# DVI_D_Out.net
KiCad netlist of a schematic drawn in Altium Designer
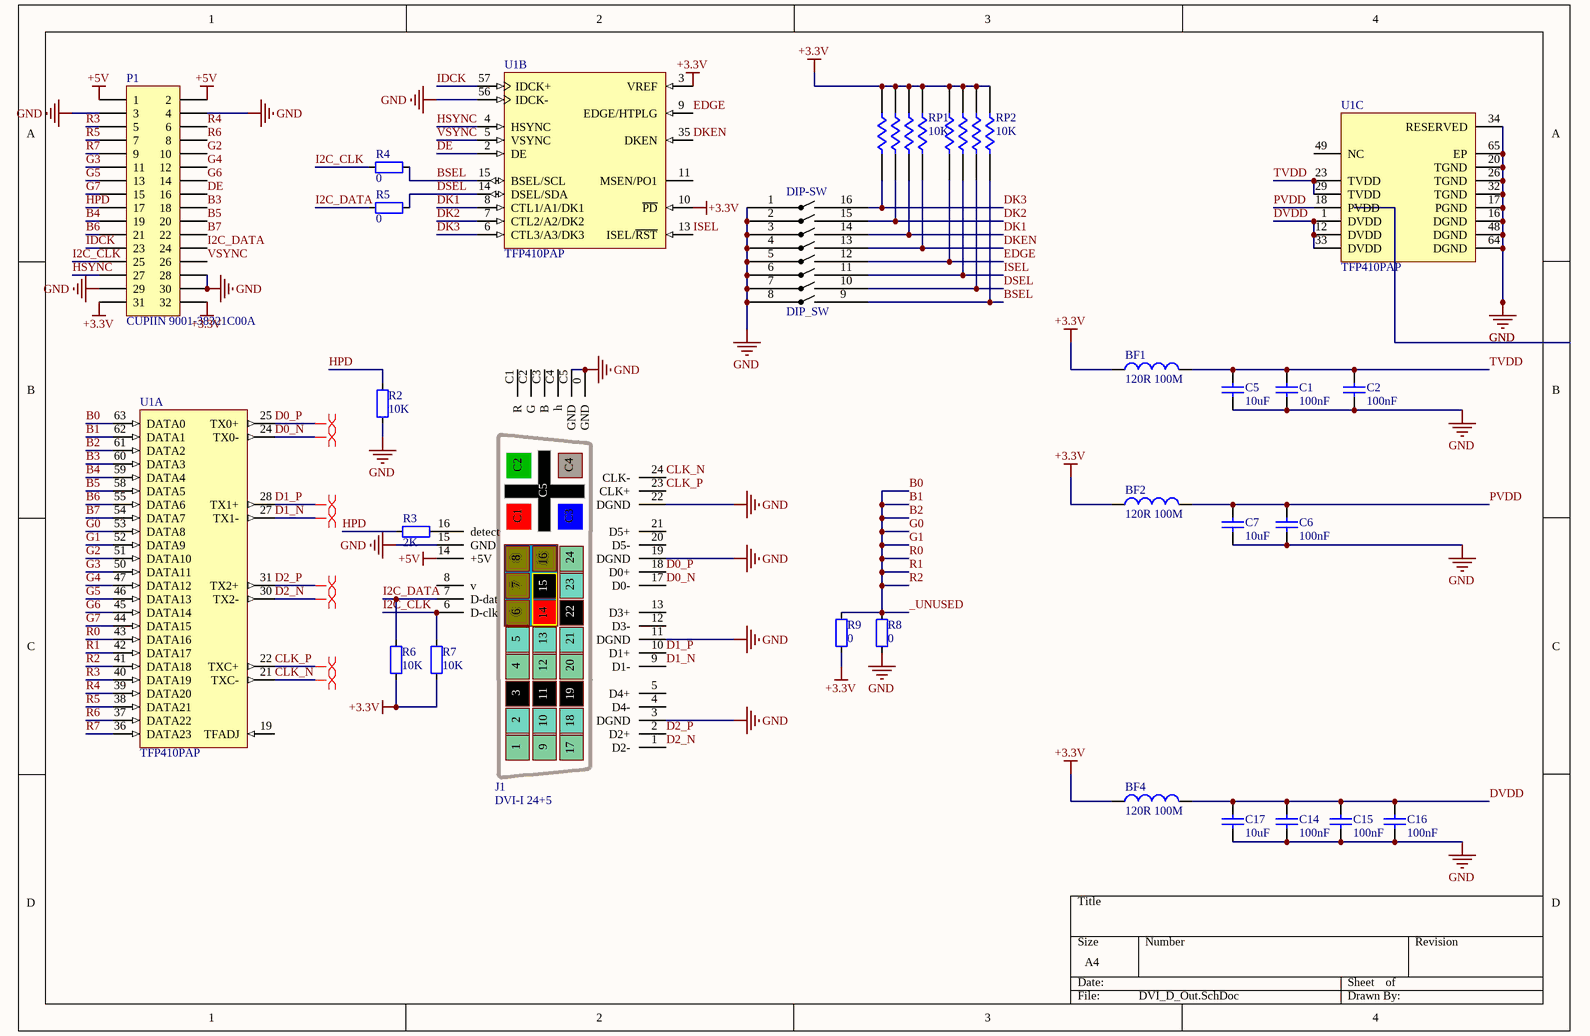
[diagram p0: DVI_D_Out.SchDoc]

(export (version "E")
  (design (tool "Eeschema 10.0.6"))
  (components
    (comp (ref "BF1")
      (value "120R 100M")
      (footprint "L-1608[0603]")
      (fields (field (name "Comment") "GZ1608D121TF") (field (name "PUBLISHER") "Altium Limited"))
      (libsource (lib "Miscellaneous Devices") (part "Inductor"))
    )
    (comp (ref "BF2")
      (value "120R 100M")
      (footprint "L-1608[0603]")
      (fields (field (name "Comment") "GZ1608D121TF") (field (name "PUBLISHER") "Altium Limited"))
      (libsource (lib "Miscellaneous Devices") (part "Inductor"))
    )
    (comp (ref "BF4")
      (value "120R 100M")
      (footprint "L-1608[0603]")
      (fields (field (name "Comment") "GZ1608D121TF") (field (name "PUBLISHER") "Altium Limited"))
      (libsource (lib "Miscellaneous Devices") (part "Inductor"))
    )
    (comp (ref "C1")
      (value "100nF")
      (footprint "C-1608[0603]")
      (description "Capacitor (Semiconductor SIM Model)")
      (fields (field (name "Comment") "Cap Semi") (field (name "PUBLISHER") "Altium Limited"))
      (libsource (lib "Miscellaneous Devices") (part "Cap Semi"))
    )
    (comp (ref "C2")
      (value "100nF")
      (footprint "C-1608[0603]")
      (description "Capacitor (Semiconductor SIM Model)")
      (fields (field (name "Comment") "Cap Semi") (field (name "PUBLISHER") "Altium Limited"))
      (libsource (lib "Miscellaneous Devices") (part "Cap Semi"))
    )
    (comp (ref "C5")
      (value "10uF")
      (footprint "C-1608[0603]")
      (description "Capacitor (Semiconductor SIM Model)")
      (fields (field (name "Comment") "Cap Semi") (field (name "PUBLISHER") "Altium Limited"))
      (libsource (lib "Miscellaneous Devices") (part "Cap Semi"))
    )
    (comp (ref "C6")
      (value "100nF")
      (footprint "C-1608[0603]")
      (description "Capacitor (Semiconductor SIM Model)")
      (fields (field (name "Comment") "Cap Semi") (field (name "PUBLISHER") "Altium Limited"))
      (libsource (lib "Miscellaneous Devices") (part "Cap Semi"))
    )
    (comp (ref "C7")
      (value "10uF")
      (footprint "C-1608[0603]")
      (description "Capacitor (Semiconductor SIM Model)")
      (fields (field (name "Comment") "Cap Semi") (field (name "PUBLISHER") "Altium Limited"))
      (libsource (lib "Miscellaneous Devices") (part "Cap Semi"))
    )
    (comp (ref "C14")
      (value "100nF")
      (footprint "C-1608[0603]")
      (description "Capacitor (Semiconductor SIM Model)")
      (fields (field (name "Comment") "Cap Semi") (field (name "PUBLISHER") "Altium Limited"))
      (libsource (lib "Miscellaneous Devices") (part "Cap Semi"))
    )
    (comp (ref "C15")
      (value "100nF")
      (footprint "C-1608[0603]")
      (description "Capacitor (Semiconductor SIM Model)")
      (fields (field (name "Comment") "Cap Semi") (field (name "PUBLISHER") "Altium Limited"))
      (libsource (lib "Miscellaneous Devices") (part "Cap Semi"))
    )
    (comp (ref "C16")
      (value "100nF")
      (footprint "C-1608[0603]")
      (description "Capacitor (Semiconductor SIM Model)")
      (fields (field (name "Comment") "Cap Semi") (field (name "PUBLISHER") "Altium Limited"))
      (libsource (lib "Miscellaneous Devices") (part "Cap Semi"))
    )
    (comp (ref "C17")
      (value "10uF")
      (footprint "C-1608[0603]")
      (description "Capacitor (Semiconductor SIM Model)")
      (fields (field (name "Comment") "Cap Semi") (field (name "PUBLISHER") "Altium Limited"))
      (libsource (lib "Miscellaneous Devices") (part "Cap Semi"))
    )
    (comp (ref "DIP-SW") (value "DIP_SW") (footprint "SO16W") (libsource (lib "Schlib1") (part "DIP_SW")))
    (comp (ref "J1") (value "DVI-I 24+5") (footprint "DVI-I") (libsource (lib "DVI-I") (part "DVI-I")))
    (comp (ref "P1")
      (value "CUPIIN 9001-38321C00A")
      (footprint "OUPIIN 9001-38321C00A")
      (description "Header, 16-Pin, Dual row")
      (fields (field (name "PUBLISHER") "Altium Limited"))
      (libsource (lib "Miscellaneous Connectors") (part "Header 16X2"))
    )
    (comp (ref "R2")
      (value "10K")
      (footprint "PCB_PassiveRes:RES_0603")
      (description "Resistor")
      (fields (field (name "Comment") "Res_0603"))
      (libsource (lib "") (part "Res_0603_1"))
    )
    (comp (ref "R3")
      (value "2K")
      (footprint "PCB_PassiveRes:RES_0603")
      (description "Resistor")
      (fields (field (name "Comment") "Res_0603"))
      (libsource (lib "") (part "Res_0603_2"))
    )
    (comp (ref "R4")
      (value "0")
      (footprint "PCB_PassiveRes:RES_0603")
      (description "Resistor")
      (fields (field (name "Comment") "Res_0603"))
      (libsource (lib "") (part "Res_0603_2"))
    )
    (comp (ref "R5")
      (value "0")
      (footprint "PCB_PassiveRes:RES_0603")
      (description "Resistor")
      (fields (field (name "Comment") "Res_0603"))
      (libsource (lib "") (part "Res_0603_2"))
    )
    (comp (ref "R6")
      (value "10K")
      (footprint "PCB_PassiveRes:RES_0603")
      (description "Resistor")
      (fields (field (name "Comment") "Res_0603"))
      (libsource (lib "SCH_Passive") (part "Res_0603"))
    )
    (comp (ref "R7")
      (value "10K")
      (footprint "PCB_PassiveRes:RES_0603")
      (description "Resistor")
      (fields (field (name "Comment") "Res_0603"))
      (libsource (lib "SCH_Passive") (part "Res_0603"))
    )
    (comp (ref "R8")
      (value "0")
      (footprint "PCB_PassiveRes:RES_0603")
      (description "Resistor")
      (fields (field (name "Comment") "Res_0603"))
      (libsource (lib "SCH_Passive") (part "Res_0603"))
    )
    (comp (ref "R9")
      (value "0")
      (footprint "PCB_PassiveRes:RES_0603")
      (description "Resistor")
      (fields (field (name "Comment") "Res_0603"))
      (libsource (lib "SCH_Passive") (part "Res_0603"))
    )
    (comp (ref "RP1") (value "10K") (footprint "R0603x4") (libsource (lib "general") (part "RPACK4")))
    (comp (ref "RP2") (value "10K") (footprint "R0603x4") (libsource (lib "general") (part "RPACK4")))
    (comp (ref "U1")
      (value "TFP410PAP")
      (footprint "PAP64-4650X4650TP_N")
      (fields (field (name "MANUFACTURER") "Texas Instruments"))
      (libsource (lib "Altium Content Vault") (part "CMP-0325-00079-1"))
    )
  )
  (nets
    (net (code "1") (name "+3.3V") (class "Default")
      (node (ref "BF1") (pin "1") (pinfunction "1_1") (pintype "passive"))
      (node (ref "BF2") (pin "1") (pinfunction "1_1") (pintype "passive"))
      (node (ref "BF4") (pin "1") (pinfunction "1_1") (pintype "passive"))
      (node (ref "P1") (pin "31") (pinfunction "31_31") (pintype "passive"))
      (node (ref "P1") (pin "32") (pinfunction "32_32") (pintype "passive"))
      (node (ref "R6") (pin "2") (pinfunction "2_2") (pintype "passive"))
      (node (ref "R7") (pin "2") (pinfunction "2_2") (pintype "passive"))
      (node (ref "R9") (pin "2") (pinfunction "2_2") (pintype "passive"))
      (node (ref "RP1") (pin "5") (pinfunction "5_5") (pintype "passive"))
      (node (ref "RP1") (pin "6") (pinfunction "6_6") (pintype "passive"))
      (node (ref "RP1") (pin "7") (pinfunction "7_7") (pintype "passive"))
      (node (ref "RP1") (pin "8") (pinfunction "8_8") (pintype "passive"))
      (node (ref "RP2") (pin "5") (pinfunction "5_5") (pintype "passive"))
      (node (ref "RP2") (pin "6") (pinfunction "6_6") (pintype "passive"))
      (node (ref "RP2") (pin "7") (pinfunction "7_7") (pintype "passive"))
      (node (ref "RP2") (pin "8") (pinfunction "8_8") (pintype "passive"))
      (node (ref "U1") (pin "10") (pinfunction "~{PD}_10") (pintype "input"))
      (node (ref "U1") (pin "3") (pinfunction "VREF_3") (pintype "input"))
    )
    (net (code "2") (name "+5V") (class "Default")
      (node (ref "J1") (pin "14") (pinfunction "+5V_14") (pintype "passive"))
      (node (ref "P1") (pin "1") (pinfunction "1_1") (pintype "passive"))
      (node (ref "P1") (pin "2") (pinfunction "2_2") (pintype "passive"))
    )
    (net (code "3") (name "/B0") (class "Default")
      (node (ref "R8") (pin "1") (pinfunction "1_1") (pintype "passive"))
      (node (ref "R9") (pin "1") (pinfunction "1_1") (pintype "passive"))
      (node (ref "U1") (pin "41") (pinfunction "DATA18_41") (pintype "input"))
      (node (ref "U1") (pin "42") (pinfunction "DATA17_42") (pintype "input"))
      (node (ref "U1") (pin "43") (pinfunction "DATA16_43") (pintype "input"))
      (node (ref "U1") (pin "52") (pinfunction "DATA9_52") (pintype "input"))
      (node (ref "U1") (pin "53") (pinfunction "DATA8_53") (pintype "input"))
      (node (ref "U1") (pin "61") (pinfunction "DATA2_61") (pintype "input"))
      (node (ref "U1") (pin "62") (pinfunction "DATA1_62") (pintype "input"))
      (node (ref "U1") (pin "63") (pinfunction "DATA0_63") (pintype "input"))
    )
    (net (code "4") (name "/B3") (class "Default")
      (node (ref "P1") (pin "18") (pinfunction "18_18") (pintype "passive"))
      (node (ref "U1") (pin "60") (pinfunction "DATA3_60") (pintype "input"))
    )
    (net (code "5") (name "/B4") (class "Default")
      (node (ref "P1") (pin "19") (pinfunction "19_19") (pintype "passive"))
      (node (ref "U1") (pin "59") (pinfunction "DATA4_59") (pintype "input"))
    )
    (net (code "6") (name "/B5") (class "Default")
      (node (ref "P1") (pin "20") (pinfunction "20_20") (pintype "passive"))
      (node (ref "U1") (pin "58") (pinfunction "DATA5_58") (pintype "input"))
    )
    (net (code "7") (name "/B6") (class "Default")
      (node (ref "P1") (pin "21") (pinfunction "21_21") (pintype "passive"))
      (node (ref "U1") (pin "55") (pinfunction "DATA6_55") (pintype "input"))
    )
    (net (code "8") (name "/B7") (class "Default")
      (node (ref "P1") (pin "22") (pinfunction "22_22") (pintype "passive"))
      (node (ref "U1") (pin "54") (pinfunction "DATA7_54") (pintype "input"))
    )
    (net (code "9") (name "/BSEL") (class "Default")
      (node (ref "DIP-SW") (pin "9") (pinfunction "9_9") (pintype "passive"))
      (node (ref "R4") (pin "1") (pinfunction "1_1") (pintype "passive"))
      (node (ref "RP2") (pin "4") (pinfunction "4_4") (pintype "passive"))
      (node (ref "U1") (pin "15") (pinfunction "BSEL/SCL_15") (pintype "bidirectional"))
    )
    (net (code "10") (name "/CLK_N") (class "Default")
      (node (ref "J1") (pin "24") (pinfunction "CLK-_24") (pintype "passive"))
      (node (ref "U1") (pin "21") (pinfunction "TXC-_21") (pintype "output"))
    )
    (net (code "11") (name "/CLK_P") (class "Default")
      (node (ref "J1") (pin "23") (pinfunction "CLK+_23") (pintype "passive"))
      (node (ref "U1") (pin "22") (pinfunction "TXC+_22") (pintype "output"))
    )
    (net (code "12") (name "/D0_N") (class "Default")
      (node (ref "J1") (pin "17") (pinfunction "D0-_17") (pintype "passive"))
      (node (ref "U1") (pin "24") (pinfunction "TX0-_24") (pintype "output"))
    )
    (net (code "13") (name "/D0_P") (class "Default")
      (node (ref "J1") (pin "18") (pinfunction "D0+_18") (pintype "passive"))
      (node (ref "U1") (pin "25") (pinfunction "TX0+_25") (pintype "output"))
    )
    (net (code "14") (name "/D1_N") (class "Default")
      (node (ref "J1") (pin "9") (pinfunction "D1-_9") (pintype "passive"))
      (node (ref "U1") (pin "27") (pinfunction "TX1-_27") (pintype "output"))
    )
    (net (code "15") (name "/D1_P") (class "Default")
      (node (ref "J1") (pin "10") (pinfunction "D1+_10") (pintype "passive"))
      (node (ref "U1") (pin "28") (pinfunction "TX1+_28") (pintype "output"))
    )
    (net (code "16") (name "/D2_N") (class "Default")
      (node (ref "J1") (pin "1") (pinfunction "D2-_1") (pintype "passive"))
      (node (ref "U1") (pin "30") (pinfunction "TX2-_30") (pintype "output"))
    )
    (net (code "17") (name "/D2_P") (class "Default")
      (node (ref "J1") (pin "2") (pinfunction "D2+_2") (pintype "passive"))
      (node (ref "U1") (pin "31") (pinfunction "TX2+_31") (pintype "output"))
    )
    (net (code "18") (name "/DE") (class "Default")
      (node (ref "P1") (pin "16") (pinfunction "16_16") (pintype "passive"))
      (node (ref "U1") (pin "2") (pinfunction "DE_2") (pintype "input"))
    )
    (net (code "19") (name "/DK1") (class "Default")
      (node (ref "DIP-SW") (pin "14") (pinfunction "14_14") (pintype "passive"))
      (node (ref "RP1") (pin "3") (pinfunction "3_3") (pintype "passive"))
      (node (ref "U1") (pin "8") (pinfunction "CTL1/A1/DK1_8") (pintype "input"))
    )
    (net (code "20") (name "/DK2") (class "Default")
      (node (ref "DIP-SW") (pin "15") (pinfunction "15_15") (pintype "passive"))
      (node (ref "RP1") (pin "2") (pinfunction "2_2") (pintype "passive"))
      (node (ref "U1") (pin "7") (pinfunction "CTL2/A2/DK2_7") (pintype "input"))
    )
    (net (code "21") (name "/DK3") (class "Default")
      (node (ref "DIP-SW") (pin "16") (pinfunction "16_16") (pintype "passive"))
      (node (ref "RP1") (pin "1") (pinfunction "1_1") (pintype "passive"))
      (node (ref "U1") (pin "6") (pinfunction "CTL3/A3/DK3_6") (pintype "input"))
    )
    (net (code "22") (name "/DKEN") (class "Default")
      (node (ref "DIP-SW") (pin "13") (pinfunction "13_13") (pintype "passive"))
      (node (ref "RP1") (pin "4") (pinfunction "4_4") (pintype "passive"))
      (node (ref "U1") (pin "35") (pinfunction "DKEN_35") (pintype "input"))
    )
    (net (code "23") (name "/DSEL") (class "Default")
      (node (ref "DIP-SW") (pin "10") (pinfunction "10_10") (pintype "passive"))
      (node (ref "R5") (pin "1") (pinfunction "1_1") (pintype "passive"))
      (node (ref "RP2") (pin "3") (pinfunction "3_3") (pintype "passive"))
      (node (ref "U1") (pin "14") (pinfunction "DSEL/SDA_14") (pintype "bidirectional"))
    )
    (net (code "24") (name "/DVDD") (class "Default")
      (node (ref "BF4") (pin "2") (pinfunction "2_2") (pintype "passive"))
      (node (ref "C14") (pin "2") (pinfunction "2_2") (pintype "passive"))
      (node (ref "C15") (pin "2") (pinfunction "2_2") (pintype "passive"))
      (node (ref "C16") (pin "2") (pinfunction "2_2") (pintype "passive"))
      (node (ref "C17") (pin "2") (pinfunction "2_2") (pintype "passive"))
      (node (ref "U1") (pin "1") (pinfunction "DVDD_1") (pintype "power_in"))
      (node (ref "U1") (pin "12") (pinfunction "DVDD_12") (pintype "power_in"))
      (node (ref "U1") (pin "33") (pinfunction "DVDD_33") (pintype "power_in"))
    )
    (net (code "25") (name "/EDGE") (class "Default")
      (node (ref "DIP-SW") (pin "12") (pinfunction "12_12") (pintype "passive"))
      (node (ref "RP2") (pin "1") (pinfunction "1_1") (pintype "passive"))
      (node (ref "U1") (pin "9") (pinfunction "EDGE/HTPLG_9") (pintype "input"))
    )
    (net (code "26") (name "/G2") (class "Default")
      (node (ref "P1") (pin "10") (pinfunction "10_10") (pintype "passive"))
      (node (ref "U1") (pin "51") (pinfunction "DATA10_51") (pintype "input"))
    )
    (net (code "27") (name "/G3") (class "Default")
      (node (ref "P1") (pin "11") (pinfunction "11_11") (pintype "passive"))
      (node (ref "U1") (pin "50") (pinfunction "DATA11_50") (pintype "input"))
    )
    (net (code "28") (name "/G4") (class "Default")
      (node (ref "P1") (pin "12") (pinfunction "12_12") (pintype "passive"))
      (node (ref "U1") (pin "47") (pinfunction "DATA12_47") (pintype "input"))
    )
    (net (code "29") (name "/G5") (class "Default")
      (node (ref "P1") (pin "13") (pinfunction "13_13") (pintype "passive"))
      (node (ref "U1") (pin "46") (pinfunction "DATA13_46") (pintype "input"))
    )
    (net (code "30") (name "/G6") (class "Default")
      (node (ref "P1") (pin "14") (pinfunction "14_14") (pintype "passive"))
      (node (ref "U1") (pin "45") (pinfunction "DATA14_45") (pintype "input"))
    )
    (net (code "31") (name "/G7") (class "Default")
      (node (ref "P1") (pin "15") (pinfunction "15_15") (pintype "passive"))
      (node (ref "U1") (pin "44") (pinfunction "DATA15_44") (pintype "input"))
    )
    (net (code "32") (name "/HPD") (class "Default")
      (node (ref "P1") (pin "17") (pinfunction "17_17") (pintype "passive"))
      (node (ref "R2") (pin "2") (pinfunction "2_2") (pintype "passive"))
      (node (ref "R3") (pin "2") (pinfunction "2_2") (pintype "passive"))
    )
    (net (code "33") (name "/HSYNC") (class "Default")
      (node (ref "P1") (pin "27") (pinfunction "27_27") (pintype "passive"))
      (node (ref "U1") (pin "4") (pinfunction "HSYNC_4") (pintype "input"))
    )
    (net (code "34") (name "/I2C_CLK") (class "Default")
      (node (ref "J1") (pin "6") (pinfunction "D-clk_6") (pintype "passive"))
      (node (ref "P1") (pin "25") (pinfunction "25_25") (pintype "passive"))
      (node (ref "R4") (pin "2") (pinfunction "2_2") (pintype "passive"))
      (node (ref "R7") (pin "1") (pinfunction "1_1") (pintype "passive"))
    )
    (net (code "35") (name "/I2C_DATA") (class "Default")
      (node (ref "J1") (pin "7") (pinfunction "D-dat_7") (pintype "passive"))
      (node (ref "P1") (pin "24") (pinfunction "24_24") (pintype "passive"))
      (node (ref "R5") (pin "2") (pinfunction "2_2") (pintype "passive"))
      (node (ref "R6") (pin "1") (pinfunction "1_1") (pintype "passive"))
    )
    (net (code "36") (name "/IDCK") (class "Default")
      (node (ref "P1") (pin "23") (pinfunction "23_23") (pintype "passive"))
      (node (ref "U1") (pin "57") (pinfunction "IDCK+_57") (pintype "input"))
    )
    (net (code "37") (name "/ISEL") (class "Default")
      (node (ref "DIP-SW") (pin "11") (pinfunction "11_11") (pintype "passive"))
      (node (ref "RP2") (pin "2") (pinfunction "2_2") (pintype "passive"))
      (node (ref "U1") (pin "13") (pinfunction "ISEL/~{RST}_13") (pintype "input"))
    )
    (net (code "38") (name "/PVDD") (class "Default")
      (node (ref "BF2") (pin "2") (pinfunction "2_2") (pintype "passive"))
      (node (ref "C6") (pin "2") (pinfunction "2_2") (pintype "passive"))
      (node (ref "C7") (pin "2") (pinfunction "2_2") (pintype "passive"))
      (node (ref "U1") (pin "18") (pinfunction "PVDD_18") (pintype "power_in"))
    )
    (net (code "39") (name "/R3") (class "Default")
      (node (ref "P1") (pin "5") (pinfunction "5_5") (pintype "passive"))
      (node (ref "U1") (pin "40") (pinfunction "DATA19_40") (pintype "input"))
    )
    (net (code "40") (name "/R4") (class "Default")
      (node (ref "P1") (pin "6") (pinfunction "6_6") (pintype "passive"))
      (node (ref "U1") (pin "39") (pinfunction "DATA20_39") (pintype "input"))
    )
    (net (code "41") (name "/R5") (class "Default")
      (node (ref "P1") (pin "7") (pinfunction "7_7") (pintype "passive"))
      (node (ref "U1") (pin "38") (pinfunction "DATA21_38") (pintype "input"))
    )
    (net (code "42") (name "/R6") (class "Default")
      (node (ref "P1") (pin "8") (pinfunction "8_8") (pintype "passive"))
      (node (ref "U1") (pin "37") (pinfunction "DATA22_37") (pintype "input"))
    )
    (net (code "43") (name "/R7") (class "Default")
      (node (ref "P1") (pin "9") (pinfunction "9_9") (pintype "passive"))
      (node (ref "U1") (pin "36") (pinfunction "DATA23_36") (pintype "input"))
    )
    (net (code "44") (name "/TVDD") (class "Default")
      (node (ref "BF1") (pin "2") (pinfunction "2_2") (pintype "passive"))
      (node (ref "C1") (pin "2") (pinfunction "2_2") (pintype "passive"))
      (node (ref "C2") (pin "2") (pinfunction "2_2") (pintype "passive"))
      (node (ref "C5") (pin "2") (pinfunction "2_2") (pintype "passive"))
      (node (ref "U1") (pin "23") (pinfunction "TVDD_23") (pintype "power_in"))
      (node (ref "U1") (pin "29") (pinfunction "TVDD_29") (pintype "power_in"))
    )
    (net (code "45") (name "/VSYNC") (class "Default")
      (node (ref "P1") (pin "26") (pinfunction "26_26") (pintype "passive"))
      (node (ref "U1") (pin "5") (pinfunction "VSYNC_5") (pintype "input"))
    )
    (net (code "46") (name "GND") (class "Default")
      (node (ref "C1") (pin "1") (pinfunction "1_1") (pintype "passive"))
      (node (ref "C14") (pin "1") (pinfunction "1_1") (pintype "passive"))
      (node (ref "C15") (pin "1") (pinfunction "1_1") (pintype "passive"))
      (node (ref "C16") (pin "1") (pinfunction "1_1") (pintype "passive"))
      (node (ref "C17") (pin "1") (pinfunction "1_1") (pintype "passive"))
      (node (ref "C2") (pin "1") (pinfunction "1_1") (pintype "passive"))
      (node (ref "C5") (pin "1") (pinfunction "1_1") (pintype "passive"))
      (node (ref "C6") (pin "1") (pinfunction "1_1") (pintype "passive"))
      (node (ref "C7") (pin "1") (pinfunction "1_1") (pintype "passive"))
      (node (ref "DIP-SW") (pin "1") (pinfunction "1_1") (pintype "passive"))
      (node (ref "DIP-SW") (pin "2") (pinfunction "2_2") (pintype "passive"))
      (node (ref "DIP-SW") (pin "3") (pinfunction "3_3") (pintype "passive"))
      (node (ref "DIP-SW") (pin "4") (pinfunction "4_4") (pintype "passive"))
      (node (ref "DIP-SW") (pin "5") (pinfunction "5_5") (pintype "passive"))
      (node (ref "DIP-SW") (pin "6") (pinfunction "6_6") (pintype "passive"))
      (node (ref "DIP-SW") (pin "7") (pinfunction "7_7") (pintype "passive"))
      (node (ref "DIP-SW") (pin "8") (pinfunction "8_8") (pintype "passive"))
      (node (ref "J1") (pin "0") (pinfunction "GND_0") (pintype "passive"))
      (node (ref "J1") (pin "11") (pinfunction "DGND_11") (pintype "passive"))
      (node (ref "J1") (pin "15") (pinfunction "GND_15") (pintype "passive"))
      (node (ref "J1") (pin "19") (pinfunction "DGND_19") (pintype "passive"))
      (node (ref "J1") (pin "22") (pinfunction "DGND_22") (pintype "passive"))
      (node (ref "J1") (pin "3") (pinfunction "DGND_3") (pintype "passive"))
      (node (ref "J1") (pin "C5") (pinfunction "GND_C5") (pintype "passive"))
      (node (ref "P1") (pin "28") (pinfunction "28_28") (pintype "passive"))
      (node (ref "P1") (pin "29") (pinfunction "29_29") (pintype "passive"))
      (node (ref "P1") (pin "3") (pinfunction "3_3") (pintype "passive"))
      (node (ref "P1") (pin "30") (pinfunction "30_30") (pintype "passive"))
      (node (ref "P1") (pin "4") (pinfunction "4_4") (pintype "passive"))
      (node (ref "R2") (pin "1") (pinfunction "1_1") (pintype "passive"))
      (node (ref "R8") (pin "2") (pinfunction "2_2") (pintype "passive"))
      (node (ref "U1") (pin "16") (pinfunction "DGND_16") (pintype "power_in"))
      (node (ref "U1") (pin "17") (pinfunction "PGND_17") (pintype "power_in"))
      (node (ref "U1") (pin "20") (pinfunction "TGND_20") (pintype "power_in"))
      (node (ref "U1") (pin "26") (pinfunction "TGND_26") (pintype "power_in"))
      (node (ref "U1") (pin "32") (pinfunction "TGND_32") (pintype "power_in"))
      (node (ref "U1") (pin "34") (pinfunction "RESERVED_34") (pintype "passive"))
      (node (ref "U1") (pin "48") (pinfunction "DGND_48") (pintype "power_in"))
      (node (ref "U1") (pin "56") (pinfunction "IDCK-_56") (pintype "input"))
      (node (ref "U1") (pin "64") (pinfunction "DGND_64") (pintype "power_in"))
      (node (ref "U1") (pin "65") (pinfunction "EP_65") (pintype "power_in"))
    )
    (net (code "47") (name "Net-(J1-detect)") (class "Default")
      (node (ref "J1") (pin "16") (pinfunction "detect_16") (pintype "passive"))
      (node (ref "R3") (pin "1") (pinfunction "1_1") (pintype "passive"))
    )
    (net (code "48") (name "unconnected-(J1-B-PadC3)") (class "Default")
      (node (ref "J1") (pin "C3") (pinfunction "B_C3") (pintype "passive"))
    )
    (net (code "49") (name "unconnected-(J1-D3+-Pad13)") (class "Default")
      (node (ref "J1") (pin "13") (pinfunction "D3+_13") (pintype "passive"))
    )
    (net (code "50") (name "unconnected-(J1-D3--Pad12)") (class "Default")
      (node (ref "J1") (pin "12") (pinfunction "D3-_12") (pintype "passive"))
    )
    (net (code "51") (name "unconnected-(J1-D4+-Pad5)") (class "Default")
      (node (ref "J1") (pin "5") (pinfunction "D4+_5") (pintype "passive"))
    )
    (net (code "52") (name "unconnected-(J1-D4--Pad4)") (class "Default")
      (node (ref "J1") (pin "4") (pinfunction "D4-_4") (pintype "passive"))
    )
    (net (code "53") (name "unconnected-(J1-D5+-Pad21)") (class "Default")
      (node (ref "J1") (pin "21") (pinfunction "D5+_21") (pintype "passive"))
    )
    (net (code "54") (name "unconnected-(J1-D5--Pad20)") (class "Default")
      (node (ref "J1") (pin "20") (pinfunction "D5-_20") (pintype "passive"))
    )
    (net (code "55") (name "unconnected-(J1-G-PadC2)") (class "Default")
      (node (ref "J1") (pin "C2") (pinfunction "G_C2") (pintype "passive"))
    )
    (net (code "56") (name "unconnected-(J1-R-PadC1)") (class "Default")
      (node (ref "J1") (pin "C1") (pinfunction "R_C1") (pintype "passive"))
    )
    (net (code "57") (name "unconnected-(J1-h-PadC4)") (class "Default")
      (node (ref "J1") (pin "C4") (pinfunction "h_C4") (pintype "passive"))
    )
    (net (code "58") (name "unconnected-(J1-v-Pad8)") (class "Default")
      (node (ref "J1") (pin "8") (pinfunction "v_8") (pintype "passive"))
    )
    (net (code "59") (name "unconnected-(U1A-TFADJ-Pad19)") (class "Default")
      (node (ref "U1") (pin "19") (pinfunction "TFADJ_19") (pintype "input"))
    )
    (net (code "60") (name "unconnected-(U1B-MSEN{slash}PO1-Pad11)") (class "Default")
      (node (ref "U1") (pin "11") (pinfunction "MSEN/PO1_11") (pintype "open_collector"))
    )
    (net (code "61") (name "unconnected-(U1C-NC-Pad49)") (class "Default")
      (node (ref "U1") (pin "49") (pinfunction "NC_49") (pintype "passive"))
    )
  )
)
